# SCH_Automatic-Irrigation-System-PBL_2025.net
KiCad netlist of a schematic drawn in EasyEDA
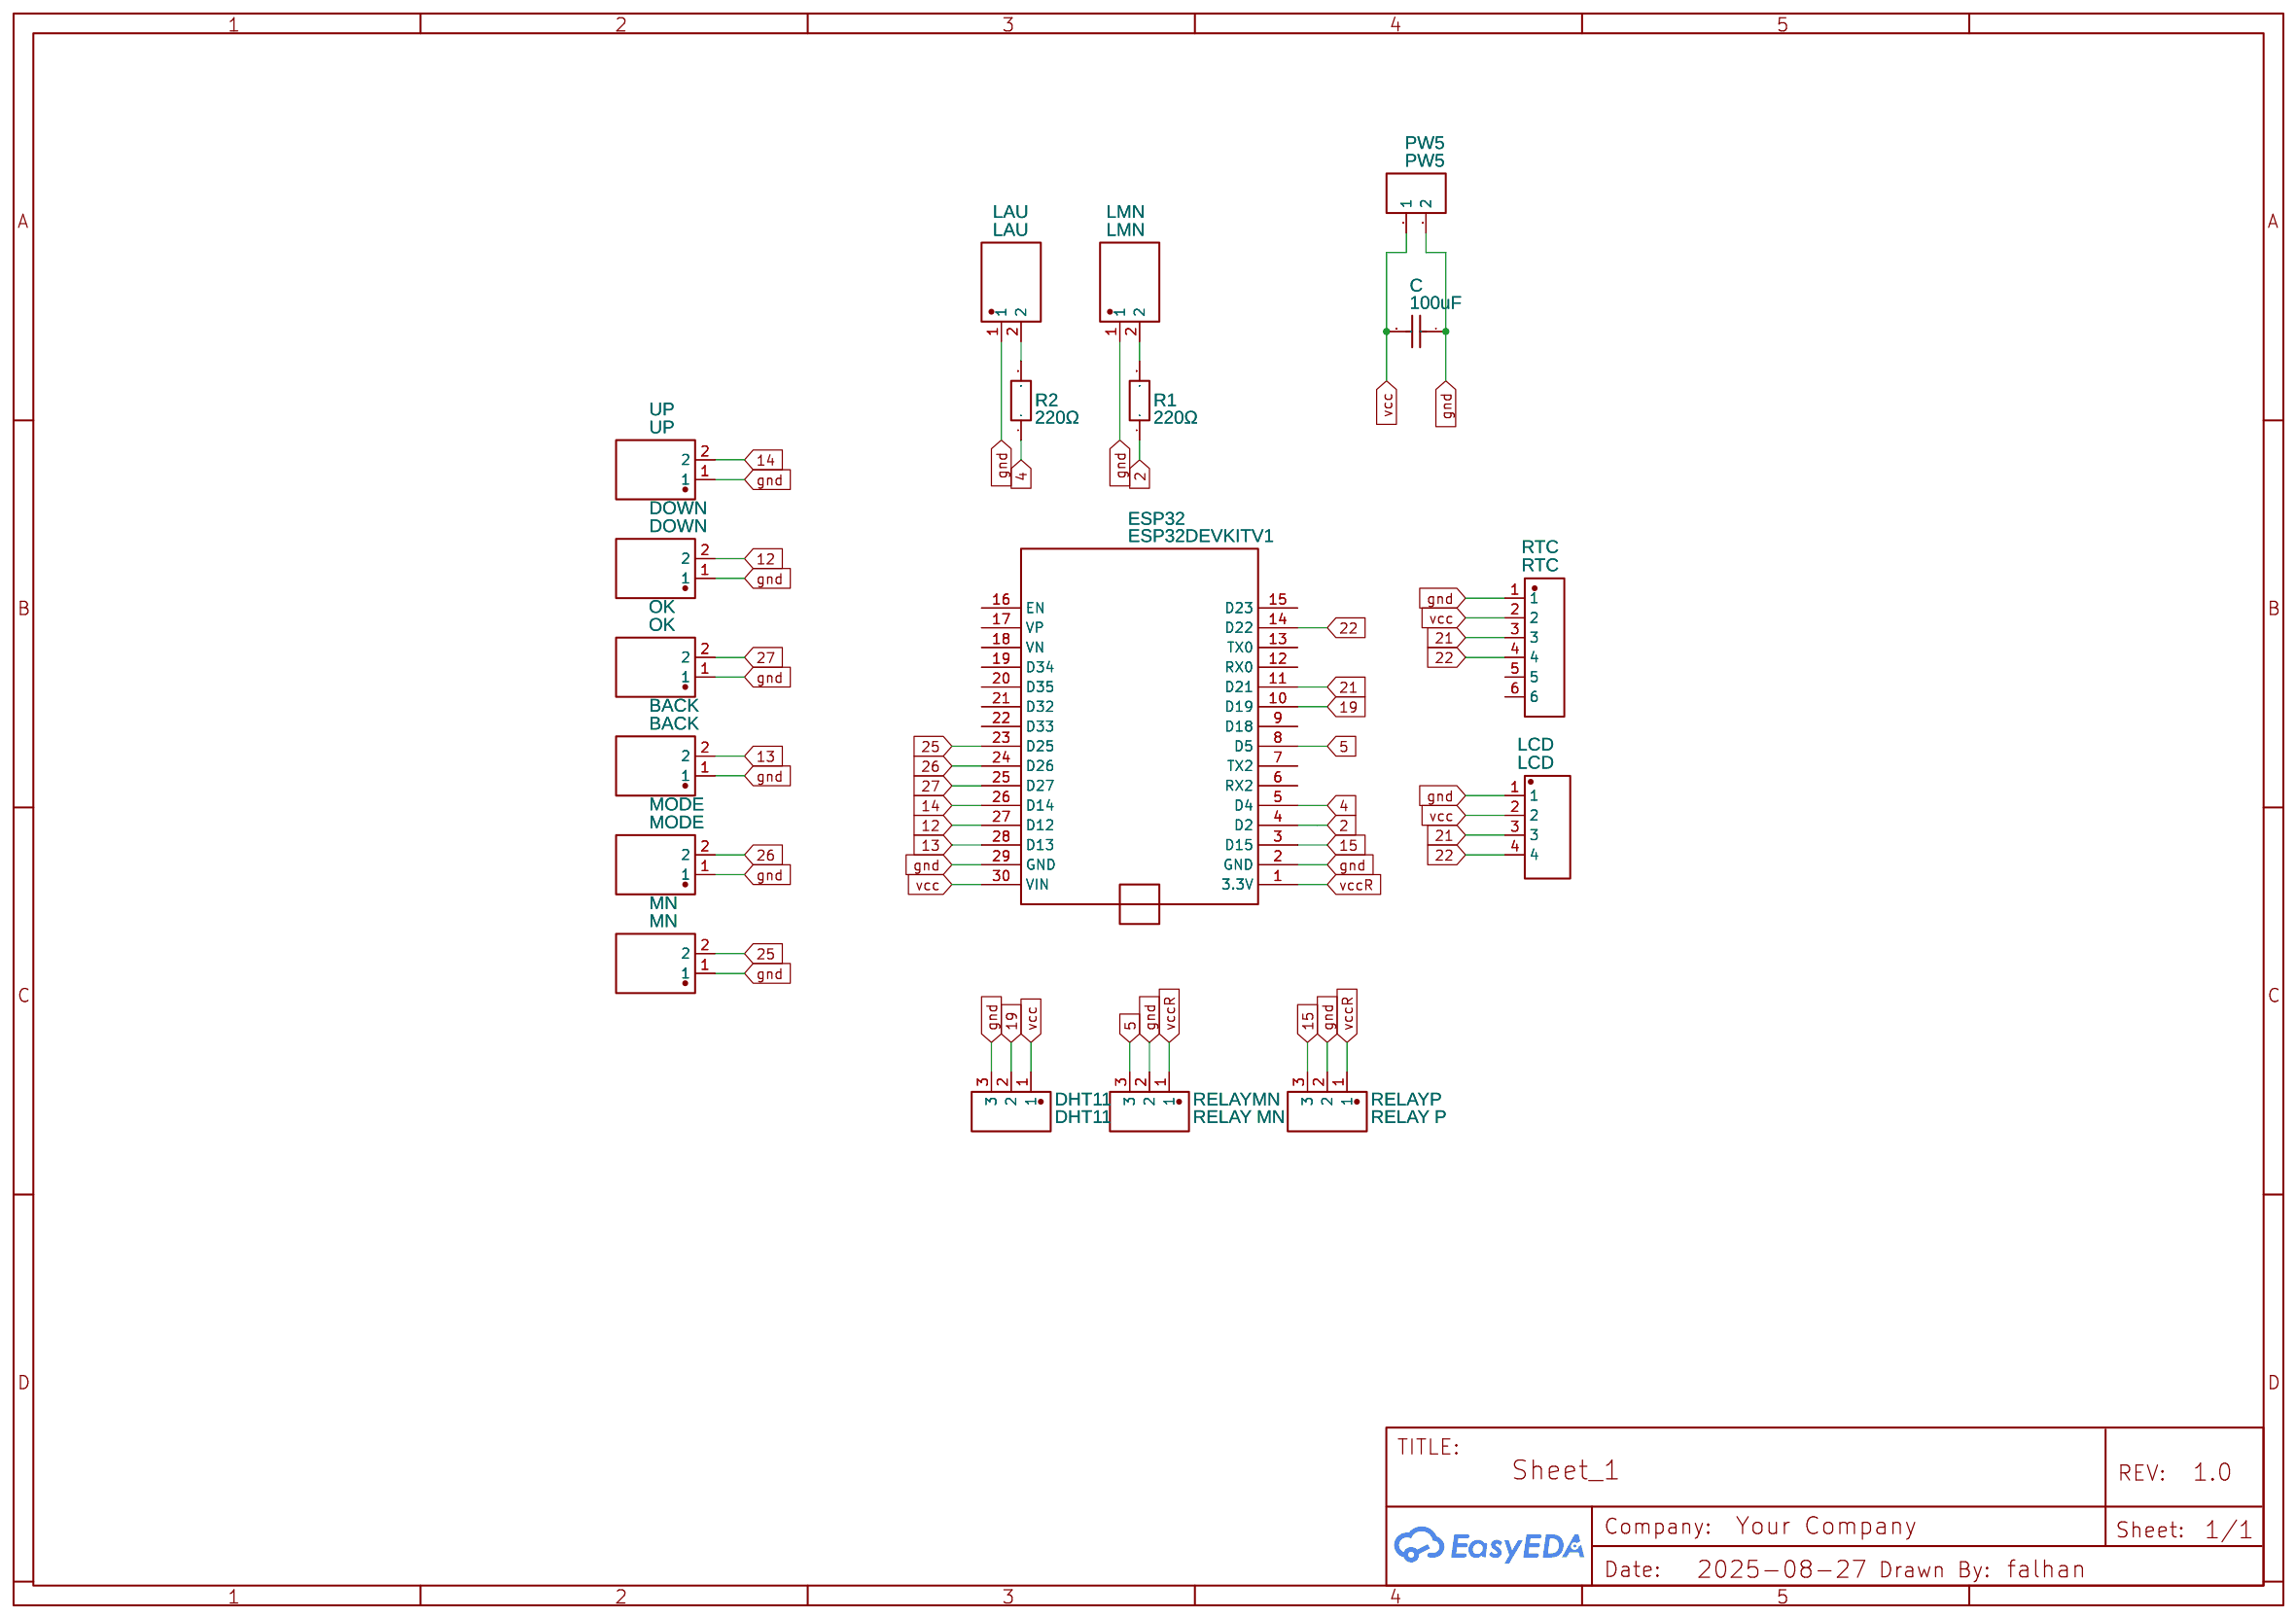
[diagram p0: schematic sheet]

(export (version "E")
  (design (tool "Eeschema 10.0.6"))
  (components
    (comp (ref "BACK")
      (value "BACK")
      (fields (field (name "Manufacturer Part") "W-2501S02P-K200") (field (name "Manufacturer") "Ckmtw(灿科盟)"))
      (libsource (lib "") (part "2501S-2P_C168996"))
    )
    (comp (ref "C")
      (value "100uF")
      (fields
        (field (name "Manufacturer Part") "1nF ±20% 250V/AC Y2Capacitor")
        (field (name "Manufacturer") "ReliaPro")
      )
      (libsource (lib "") (part "1nF ±20% 250V/AC Y2Capacitor"))
    )
    (comp (ref "DHT11")
      (value "DHT11")
      (fields
        (field (name "Manufacturer Part") "ZX-XH2.54-3PZZ")
        (field (name "Manufacturer") "Megastar(兆星)")
      )
      (libsource (lib "") (part "ZX-XH2.54-3PZZ_2"))
    )
    (comp (ref "DOWN")
      (value "DOWN")
      (fields (field (name "Manufacturer Part") "W-2501S02P-K200") (field (name "Manufacturer") "Ckmtw(灿科盟)"))
      (libsource (lib "") (part "2501S-2P_C168996_3"))
    )
    (comp (ref "ESP32") (value "ESP32DEVKITV1") (libsource (lib "") (part "ESP32DEVKITV1")))
    (comp (ref "LAU")
      (value "LAU")
      (fields (field (name "Manufacturer Part") "W-2501S02P-K200") (field (name "Manufacturer") "Ckmtw(灿科盟)"))
      (libsource (lib "") (part "2501S-2P_C168996_6"))
    )
    (comp (ref "LCD")
      (value "LCD")
      (fields (field (name "Manufacturer Part") "W-2501S04P-K000") (field (name "Manufacturer") "Ckmtw(灿科盟)"))
      (libsource (lib "") (part "2501S-4P_C125328"))
    )
    (comp (ref "LMN")
      (value "LMN")
      (fields (field (name "Manufacturer Part") "W-2501S02P-K200") (field (name "Manufacturer") "Ckmtw(灿科盟)"))
      (libsource (lib "") (part "2501S-2P_C168996_7"))
    )
    (comp (ref "MN")
      (value "MN")
      (fields (field (name "Manufacturer Part") "W-2501S02P-K200") (field (name "Manufacturer") "Ckmtw(灿科盟)"))
      (libsource (lib "") (part "2501S-2P_C168996_4"))
    )
    (comp (ref "MODE")
      (value "MODE")
      (fields (field (name "Manufacturer Part") "W-2501S02P-K200") (field (name "Manufacturer") "Ckmtw(灿科盟)"))
      (libsource (lib "") (part "2501S-2P_C168996_1"))
    )
    (comp (ref "OK")
      (value "OK")
      (fields (field (name "Manufacturer Part") "W-2501S02P-K200") (field (name "Manufacturer") "Ckmtw(灿科盟)"))
      (libsource (lib "") (part "2501S-2P_C168996_2"))
    )
    (comp (ref "PW5") (value "PW5") (libsource (lib "") (part "CONN-TH_2P-P5.00")))
    (comp (ref "R1")
      (value "220Ω")
      (fields
        (field (name "Manufacturer Part") "RN1/4W10KFT/BA1")
        (field (name "Manufacturer") "Tyohm(幸亚电阻)")
      )
      (libsource (lib "") (part "RN 1/4W 10K F T/B A1"))
    )
    (comp (ref "R2")
      (value "220Ω")
      (fields
        (field (name "Manufacturer Part") "RN1/4W10KFT/BA1")
        (field (name "Manufacturer") "Tyohm(幸亚电阻)")
      )
      (libsource (lib "") (part "RN 1/4W 10K F T/B A1"))
    )
    (comp (ref "RELAYMN")
      (value "RELAY MN")
      (fields
        (field (name "Manufacturer Part") "ZX-XH2.54-3PZZ")
        (field (name "Manufacturer") "Megastar(兆星)")
      )
      (libsource (lib "") (part "ZX-XH2.54-3PZZ_1"))
    )
    (comp (ref "RELAYP")
      (value "RELAY P")
      (fields
        (field (name "Manufacturer Part") "ZX-XH2.54-3PZZ")
        (field (name "Manufacturer") "Megastar(兆星)")
      )
      (libsource (lib "") (part "ZX-XH2.54-3PZZ"))
    )
    (comp (ref "RTC")
      (value "RTC")
      (fields (field (name "Manufacturer Part") "2.54-1*6P母") (field (name "Manufacturer") "BOOMELE(博穆精密)"))
      (libsource (lib "") (part "Header-Female-2.54_1x6"))
    )
    (comp (ref "UP")
      (value "UP")
      (fields (field (name "Manufacturer Part") "W-2501S02P-K200") (field (name "Manufacturer") "Ckmtw(灿科盟)"))
      (libsource (lib "") (part "2501S-2P_C168996_5"))
    )
  )
  (nets
    (net (code "1") (name "2") (class "Default")
      (node (ref "ESP32") (pin "4") (pinfunction "D2_4") (pintype "unspecified"))
      (node (ref "R1") (pin "1") (pinfunction "1_1") (pintype "unspecified"))
    )
    (net (code "2") (name "4") (class "Default")
      (node (ref "ESP32") (pin "5") (pinfunction "D4_5") (pintype "unspecified"))
      (node (ref "R2") (pin "1") (pinfunction "1_1") (pintype "unspecified"))
    )
    (net (code "3") (name "5") (class "Default")
      (node (ref "ESP32") (pin "8") (pinfunction "D5_8") (pintype "unspecified"))
      (node (ref "RELAYMN") (pin "3") (pinfunction "3_3") (pintype "unspecified"))
    )
    (net (code "4") (name "12") (class "Default")
      (node (ref "DOWN") (pin "2") (pinfunction "2_2") (pintype "unspecified"))
      (node (ref "ESP32") (pin "27") (pinfunction "D12_27") (pintype "unspecified"))
    )
    (net (code "5") (name "13") (class "Default")
      (node (ref "BACK") (pin "2") (pinfunction "2_2") (pintype "unspecified"))
      (node (ref "ESP32") (pin "28") (pinfunction "D13_28") (pintype "unspecified"))
    )
    (net (code "6") (name "14") (class "Default")
      (node (ref "ESP32") (pin "26") (pinfunction "D14_26") (pintype "unspecified"))
      (node (ref "UP") (pin "2") (pinfunction "2_2") (pintype "unspecified"))
    )
    (net (code "7") (name "15") (class "Default")
      (node (ref "ESP32") (pin "3") (pinfunction "D15_3") (pintype "unspecified"))
      (node (ref "RELAYP") (pin "3") (pinfunction "3_3") (pintype "unspecified"))
    )
    (net (code "8") (name "19") (class "Default")
      (node (ref "DHT11") (pin "2") (pinfunction "2_2") (pintype "unspecified"))
      (node (ref "ESP32") (pin "10") (pinfunction "D19_10") (pintype "unspecified"))
    )
    (net (code "9") (name "21") (class "Default")
      (node (ref "ESP32") (pin "11") (pinfunction "D21_11") (pintype "unspecified"))
      (node (ref "LCD") (pin "3") (pinfunction "3_3") (pintype "unspecified"))
      (node (ref "RTC") (pin "3") (pinfunction "3_3") (pintype "unspecified"))
    )
    (net (code "10") (name "22") (class "Default")
      (node (ref "ESP32") (pin "14") (pinfunction "D22_14") (pintype "unspecified"))
      (node (ref "LCD") (pin "4") (pinfunction "4_4") (pintype "unspecified"))
      (node (ref "RTC") (pin "4") (pinfunction "4_4") (pintype "unspecified"))
    )
    (net (code "11") (name "25") (class "Default")
      (node (ref "ESP32") (pin "23") (pinfunction "D25_23") (pintype "unspecified"))
      (node (ref "MN") (pin "2") (pinfunction "2_2") (pintype "unspecified"))
    )
    (net (code "12") (name "26") (class "Default")
      (node (ref "ESP32") (pin "24") (pinfunction "D26_24") (pintype "unspecified"))
      (node (ref "MODE") (pin "2") (pinfunction "2_2") (pintype "unspecified"))
    )
    (net (code "13") (name "27") (class "Default")
      (node (ref "ESP32") (pin "25") (pinfunction "D27_25") (pintype "unspecified"))
      (node (ref "OK") (pin "2") (pinfunction "2_2") (pintype "unspecified"))
    )
    (net (code "14") (name "Net-(LAU-Pad2)") (class "Default")
      (node (ref "LAU") (pin "2") (pinfunction "2_2") (pintype "unspecified"))
      (node (ref "R2") (pin "2") (pinfunction "2_2") (pintype "unspecified"))
    )
    (net (code "15") (name "Net-(LMN-Pad2)") (class "Default")
      (node (ref "LMN") (pin "2") (pinfunction "2_2") (pintype "unspecified"))
      (node (ref "R1") (pin "2") (pinfunction "2_2") (pintype "unspecified"))
    )
    (net (code "16") (name "gnd") (class "Default")
      (node (ref "BACK") (pin "1") (pinfunction "1_1") (pintype "unspecified"))
      (node (ref "C") (pin "1") (pinfunction "1_1") (pintype "input"))
      (node (ref "DHT11") (pin "3") (pinfunction "3_3") (pintype "unspecified"))
      (node (ref "DOWN") (pin "1") (pinfunction "1_1") (pintype "unspecified"))
      (node (ref "ESP32") (pin "2") (pinfunction "GND_2") (pintype "unspecified"))
      (node (ref "ESP32") (pin "29") (pinfunction "GND_29") (pintype "unspecified"))
      (node (ref "LAU") (pin "1") (pinfunction "1_1") (pintype "unspecified"))
      (node (ref "LCD") (pin "1") (pinfunction "1_1") (pintype "unspecified"))
      (node (ref "LMN") (pin "1") (pinfunction "1_1") (pintype "unspecified"))
      (node (ref "MN") (pin "1") (pinfunction "1_1") (pintype "unspecified"))
      (node (ref "MODE") (pin "1") (pinfunction "1_1") (pintype "unspecified"))
      (node (ref "OK") (pin "1") (pinfunction "1_1") (pintype "unspecified"))
      (node (ref "PW5") (pin "2") (pinfunction "2_2") (pintype "unspecified"))
      (node (ref "RELAYMN") (pin "2") (pinfunction "2_2") (pintype "unspecified"))
      (node (ref "RELAYP") (pin "2") (pinfunction "2_2") (pintype "unspecified"))
      (node (ref "RTC") (pin "1") (pinfunction "1_1") (pintype "unspecified"))
      (node (ref "UP") (pin "1") (pinfunction "1_1") (pintype "unspecified"))
    )
    (net (code "17") (name "unconnected-(ESP32-D18-Pad9)") (class "Default")
      (node (ref "ESP32") (pin "9") (pinfunction "D18_9") (pintype "unspecified"))
    )
    (net (code "18") (name "unconnected-(ESP32-D23-Pad15)") (class "Default")
      (node (ref "ESP32") (pin "15") (pinfunction "D23_15") (pintype "unspecified"))
    )
    (net (code "19") (name "unconnected-(ESP32-D32-Pad21)") (class "Default")
      (node (ref "ESP32") (pin "21") (pinfunction "D32_21") (pintype "unspecified"))
    )
    (net (code "20") (name "unconnected-(ESP32-D33-Pad22)") (class "Default")
      (node (ref "ESP32") (pin "22") (pinfunction "D33_22") (pintype "unspecified"))
    )
    (net (code "21") (name "unconnected-(ESP32-D34-Pad19)") (class "Default")
      (node (ref "ESP32") (pin "19") (pinfunction "D34_19") (pintype "unspecified"))
    )
    (net (code "22") (name "unconnected-(ESP32-D35-Pad20)") (class "Default")
      (node (ref "ESP32") (pin "20") (pinfunction "D35_20") (pintype "unspecified"))
    )
    (net (code "23") (name "unconnected-(ESP32-EN-Pad16)") (class "Default")
      (node (ref "ESP32") (pin "16") (pinfunction "EN_16") (pintype "unspecified"))
    )
    (net (code "24") (name "unconnected-(ESP32-RX0-Pad12)") (class "Default")
      (node (ref "ESP32") (pin "12") (pinfunction "RX0_12") (pintype "unspecified"))
    )
    (net (code "25") (name "unconnected-(ESP32-RX2-Pad6)") (class "Default")
      (node (ref "ESP32") (pin "6") (pinfunction "RX2_6") (pintype "unspecified"))
    )
    (net (code "26") (name "unconnected-(ESP32-TX0-Pad13)") (class "Default")
      (node (ref "ESP32") (pin "13") (pinfunction "TX0_13") (pintype "unspecified"))
    )
    (net (code "27") (name "unconnected-(ESP32-TX2-Pad7)") (class "Default")
      (node (ref "ESP32") (pin "7") (pinfunction "TX2_7") (pintype "unspecified"))
    )
    (net (code "28") (name "unconnected-(ESP32-VN-Pad18)") (class "Default")
      (node (ref "ESP32") (pin "18") (pinfunction "VN_18") (pintype "unspecified"))
    )
    (net (code "29") (name "unconnected-(ESP32-VP-Pad17)") (class "Default")
      (node (ref "ESP32") (pin "17") (pinfunction "VP_17") (pintype "unspecified"))
    )
    (net (code "30") (name "unconnected-(RTC-Pad5)") (class "Default")
      (node (ref "RTC") (pin "5") (pinfunction "5_5") (pintype "unspecified"))
    )
    (net (code "31") (name "unconnected-(RTC-Pad6)") (class "Default")
      (node (ref "RTC") (pin "6") (pinfunction "6_6") (pintype "unspecified"))
    )
    (net (code "32") (name "vcc") (class "Default")
      (node (ref "C") (pin "2") (pinfunction "2_2") (pintype "input"))
      (node (ref "DHT11") (pin "1") (pinfunction "1_1") (pintype "unspecified"))
      (node (ref "ESP32") (pin "30") (pinfunction "VIN_30") (pintype "unspecified"))
      (node (ref "LCD") (pin "2") (pinfunction "2_2") (pintype "unspecified"))
      (node (ref "PW5") (pin "1") (pinfunction "1_1") (pintype "unspecified"))
      (node (ref "RTC") (pin "2") (pinfunction "2_2") (pintype "unspecified"))
    )
    (net (code "33") (name "vccR") (class "Default")
      (node (ref "ESP32") (pin "1") (pinfunction "3.3V_1") (pintype "unspecified"))
      (node (ref "RELAYMN") (pin "1") (pinfunction "1_1") (pintype "unspecified"))
      (node (ref "RELAYP") (pin "1") (pinfunction "1_1") (pintype "unspecified"))
    )
  )
)
